# ShineSensor.net
KiCad netlist of a schematic drawn in EAGLE
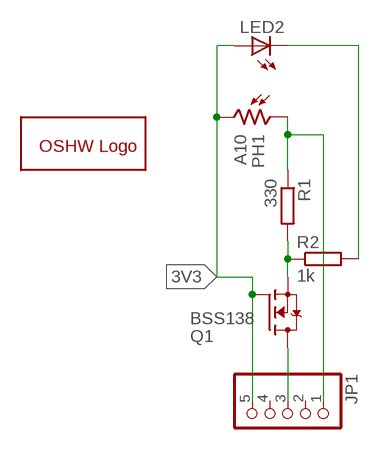
[diagram p0: schematic, sheet 1]

(export (version "E")
  (design (tool "Eeschema 10.0.6"))
  (components
    (comp (ref "JP1")
      (value "PINHD-1X5")
      (footprint "eagle-import:1X05")
      (libsource (lib "eagle-import") (part "PINHD-1X5"))
    )
    (comp (ref "LED2")
      (value "LEDSMT1206")
      (footprint "eagle-import:1206")
      (libsource (lib "eagle-import") (part "LEDSMT1206"))
    )
    (comp (ref "PH1")
      (value "A10")
      (footprint "eagle-import:T0-46-A10XX")
      (libsource (lib "eagle-import") (part "A1050_11"))
    )
    (comp (ref "Q1")
      (value "BSS138")
      (footprint "eagle-import:SOT23")
      (fields (field (name "MF") "Fairchild"))
      (libsource (lib "eagle-import") (part "BSS138"))
    )
    (comp (ref "R1")
      (value "330")
      (footprint "eagle-import:R1206")
      (libsource (lib "eagle-import") (part "R-EU_R1206"))
    )
    (comp (ref "R2")
      (value "1k")
      (footprint "eagle-import:R1206")
      (libsource (lib "eagle-import") (part "R-EU_R1206"))
    )
    (comp (ref "U$1")
      (value "OPENSOURCE")
      (footprint "eagle-import:OSHW_5MM")
      (libsource (lib "eagle-import") (part "OPENSOURCE"))
    )
  )
  (nets
    (net (code "1") (name "3V3") (class "Default")
      (node (ref "JP1") (pin "5") (pinfunction "5_5") (pintype "passive"))
      (node (ref "LED2") (pin "A") (pinfunction "A_A") (pintype "passive"))
      (node (ref "PH1") (pin "2") (pinfunction "2_2") (pintype "passive"))
      (node (ref "Q1") (pin "1") (pinfunction "G_1") (pintype "passive"))
    )
    (net (code "2") (name "Net-(JP1-Pad1)") (class "Default")
      (node (ref "JP1") (pin "1") (pinfunction "1_1") (pintype "passive"))
      (node (ref "PH1") (pin "1") (pinfunction "1_1") (pintype "passive"))
      (node (ref "R1") (pin "1") (pinfunction "1_1") (pintype "passive"))
    )
    (net (code "3") (name "Net-(LED2-PadC)") (class "Default")
      (node (ref "LED2") (pin "C") (pinfunction "C_C") (pintype "passive"))
      (node (ref "R2") (pin "2") (pinfunction "2_2") (pintype "passive"))
    )
    (net (code "4") (name "Net-(Q1-D)") (class "Default")
      (node (ref "JP1") (pin "3") (pinfunction "3_3") (pintype "passive"))
      (node (ref "Q1") (pin "3") (pinfunction "D_3") (pintype "passive"))
    )
    (net (code "5") (name "Net-(Q1-S)") (class "Default")
      (node (ref "Q1") (pin "2") (pinfunction "S_2") (pintype "passive"))
      (node (ref "R1") (pin "2") (pinfunction "2_2") (pintype "passive"))
      (node (ref "R2") (pin "1") (pinfunction "1_1") (pintype "passive"))
    )
    (net (code "6") (name "unconnected-(JP1-Pad2)") (class "Default")
      (node (ref "JP1") (pin "2") (pinfunction "2_2") (pintype "passive"))
    )
    (net (code "7") (name "unconnected-(JP1-Pad4)") (class "Default")
      (node (ref "JP1") (pin "4") (pinfunction "4_4") (pintype "passive"))
    )
  )
)
